# 3DChameleonMK7_2024-11-28.net
KiCad netlist of a schematic drawn in Altium Designer
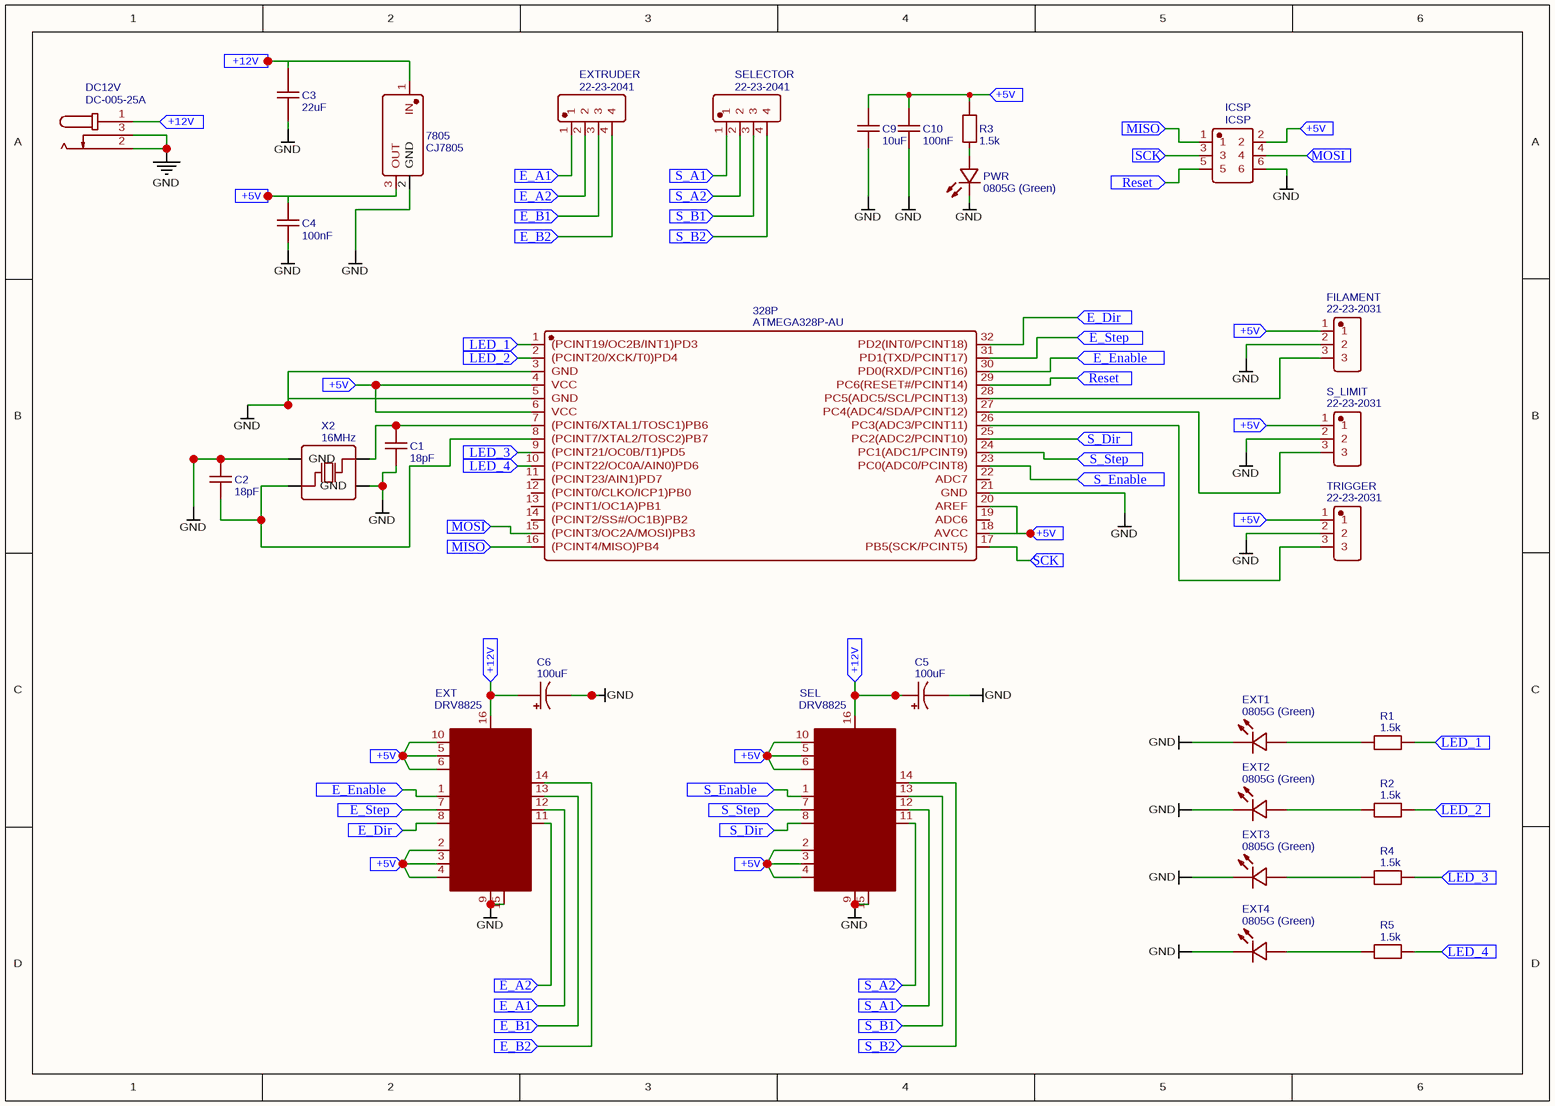
[diagram p0: 3DChameleonMK7_2024-11-28.schdoc]

(export (version "E")
  (design (tool "Eeschema 10.0.6"))
  (components
    (comp (ref "328P")
      (value "ATMEGA328P-AU")
      (fields (field (name "MANUFACTURER") "MICROCHIP"))
      (libsource (lib "altium-import") (part "root_0_ATMEGA328P-AU_"))
    )
    (comp (ref "7805")
      (value "CJ7805")
      (fields (field (name "MANUFACTURER") "CJ") (field (name "CONTRIBUTOR") "LCSC"))
      (libsource (lib "altium-import") (part "root_3_CJ7805_"))
    )
    (comp (ref "C1")
      (value "18pF")
      (fields (field (name "MANUFACTURER") "Zhejiang Abel Elec"))
      (libsource (lib "altium-import") (part "root_1_18pF_"))
    )
    (comp (ref "C2")
      (value "18pF")
      (fields (field (name "MANUFACTURER") "Zhejiang Abel Elec"))
      (libsource (lib "altium-import") (part "root_1_18pF_"))
    )
    (comp (ref "C3")
      (value "22uF")
      (fields (field (name "MANUFACTURER") "SAMSUNG") (field (name "MANUFACTURER PART") "CL21A226MAQNNNE"))
      (libsource (lib "altium-import") (part "root_1_22uF_"))
    )
    (comp (ref "C4")
      (value "100nF")
      (fields (field (name "MANUFACTURER PART") "CL21B104JBCNNNC") (field (name "MANUFACTURER") "SAMSUNG"))
      (libsource (lib "altium-import") (part "root_1_100nF_"))
    )
    (comp (ref "C5")
      (value "100uF")
      (fields
        (field (name "MANUFACTURER") "CEC")
        (field (name "MANUFACTURER PART") "CA45-B-6.3V-100uF-K")
        (field (name "CONTRIBUTOR") "LCSC")
      )
      (libsource (lib "altium-import") (part "root_1_100uF_"))
    )
    (comp (ref "C6")
      (value "100uF")
      (fields
        (field (name "MANUFACTURER") "CEC")
        (field (name "MANUFACTURER PART") "CA45-B-6.3V-100uF-K")
        (field (name "CONTRIBUTOR") "LCSC")
      )
      (libsource (lib "altium-import") (part "root_1_100uF_"))
    )
    (comp (ref "C9")
      (value "10uF")
      (fields (field (name "MANUFACTURER PART") "CL21A106KAYNNNE") (field (name "MANUFACTURER") "SAMSUNG"))
      (libsource (lib "altium-import") (part "root_1_10uF_"))
    )
    (comp (ref "C10")
      (value "100nF")
      (fields (field (name "MANUFACTURER PART") "CL21B104JBCNNNC") (field (name "MANUFACTURER") "SAMSUNG"))
      (libsource (lib "altium-import") (part "root_1_100nF_"))
    )
    (comp (ref "DC12V")
      (value "DC-005-25A")
      (fields (field (name "MANUFACTURER") "HRO") (field (name "CONTRIBUTOR") "LCSC"))
      (libsource (lib "altium-import") (part "root_0_DC-005-25A_"))
    )
    (comp (ref "EXT")
      (value "DRV8825")
      (fields (field (name "CONTRIBUTOR") "OldJeffer"))
      (libsource (lib "altium-import") (part "root_0_DRV8825_"))
    )
    (comp (ref "EXT1")
      (value "0805G (Green)")
      (fields (field (name "MANUFACTURER") "KENTO"))
      (libsource (lib "altium-import") (part "root_0_0805G (Green)_"))
    )
    (comp (ref "EXT2")
      (value "0805G (Green)")
      (fields (field (name "MANUFACTURER") "KENTO"))
      (libsource (lib "altium-import") (part "root_0_0805G (Green)_"))
    )
    (comp (ref "EXT3")
      (value "0805G (Green)")
      (fields (field (name "MANUFACTURER") "KENTO"))
      (libsource (lib "altium-import") (part "root_0_0805G (Green)_"))
    )
    (comp (ref "EXT4")
      (value "0805G (Green)")
      (fields (field (name "MANUFACTURER") "KENTO"))
      (libsource (lib "altium-import") (part "root_0_0805G (Green)_"))
    )
    (comp (ref "EXTRUDER")
      (value "22-23-2041")
      (fields (field (name "MANUFACTURER") "MOLEX") (field (name "CONTRIBUTOR") "LCSC"))
      (libsource (lib "altium-import") (part "root_1_22-23-2041_"))
    )
    (comp (ref "FILAMENT")
      (value "22-23-2031")
      (fields (field (name "MANUFACTURER") "MOLEX") (field (name "CONTRIBUTOR") "LCSC"))
      (libsource (lib "altium-import") (part "root_0_22-23-2031_"))
    )
    (comp (ref "ICSP")
      (value "ICSP")
      (fields
        (field (name "MANUFACTURER") "ReliaPro")
        (field (name "MANUFACTURER PART") "Female header/2.54mm2x3 Female header")
      )
      (libsource (lib "altium-import") (part "root_0_ICSP_"))
    )
    (comp (ref "PWR")
      (value "0805G (Green)")
      (fields (field (name "MANUFACTURER") "KENTO"))
      (libsource (lib "altium-import") (part "root_1_0805G (Green)_"))
    )
    (comp (ref "R1")
      (value "1.5k")
      (fields
        (field (name "MANUFACTURER") "RALEC")
        (field (name "MANUFACTURER PART") "RAT034700FTP")
        (field (name "CONTRIBUTOR") "LCSC")
      )
      (libsource (lib "altium-import") (part "root_2_1.5k_"))
    )
    (comp (ref "R2")
      (value "1.5k")
      (fields
        (field (name "MANUFACTURER") "RALEC")
        (field (name "MANUFACTURER PART") "RAT034700FTP")
        (field (name "CONTRIBUTOR") "LCSC")
      )
      (libsource (lib "altium-import") (part "root_2_1.5k_"))
    )
    (comp (ref "R3")
      (value "1.5k")
      (fields
        (field (name "MANUFACTURER") "RALEC")
        (field (name "MANUFACTURER PART") "RAT034700FTP")
        (field (name "CONTRIBUTOR") "LCSC")
      )
      (libsource (lib "altium-import") (part "root_1_1.5k_"))
    )
    (comp (ref "R4")
      (value "1.5k")
      (fields
        (field (name "MANUFACTURER") "RALEC")
        (field (name "MANUFACTURER PART") "RAT034700FTP")
        (field (name "CONTRIBUTOR") "LCSC")
      )
      (libsource (lib "altium-import") (part "root_2_1.5k_"))
    )
    (comp (ref "R5")
      (value "1.5k")
      (fields
        (field (name "MANUFACTURER") "RALEC")
        (field (name "MANUFACTURER PART") "RAT034700FTP")
        (field (name "CONTRIBUTOR") "LCSC")
      )
      (libsource (lib "altium-import") (part "root_2_1.5k_"))
    )
    (comp (ref "SEL")
      (value "DRV8825")
      (fields (field (name "CONTRIBUTOR") "OldJeffer"))
      (libsource (lib "altium-import") (part "root_0_DRV8825_"))
    )
    (comp (ref "SELECTOR")
      (value "22-23-2041")
      (fields (field (name "MANUFACTURER") "MOLEX") (field (name "CONTRIBUTOR") "LCSC"))
      (libsource (lib "altium-import") (part "root_1_22-23-2041_"))
    )
    (comp (ref "S_LIMIT")
      (value "22-23-2031")
      (fields (field (name "MANUFACTURER") "MOLEX") (field (name "CONTRIBUTOR") "LCSC"))
      (libsource (lib "altium-import") (part "root_0_22-23-2031_"))
    )
    (comp (ref "TRIGGER")
      (value "22-23-2031")
      (fields (field (name "MANUFACTURER") "MOLEX") (field (name "CONTRIBUTOR") "LCSC"))
      (libsource (lib "altium-import") (part "root_0_22-23-2031_"))
    )
    (comp (ref "X2")
      (value "16MHz")
      (fields
        (field (name "MANUFACTURER") "ZheJiang East Crystal Elec")
        (field (name "MANUFACTURER PART") "M16000B222")
        (field (name "CONTRIBUTOR") "LCSC")
      )
      (libsource (lib "altium-import") (part "root_0_16MHz_"))
    )
  )
  (nets
    (net (code "1") (name "/+5V") (class "Default")
      (node (ref "328P") (pin "18") (pinfunction "AVCC_18") (pintype "passive"))
      (node (ref "328P") (pin "20") (pinfunction "AREF_20") (pintype "passive"))
      (node (ref "328P") (pin "4") (pinfunction "VCC_4") (pintype "passive"))
      (node (ref "328P") (pin "6") (pinfunction "VCC_6") (pintype "passive"))
      (node (ref "7805") (pin "3") (pinfunction "OUT_3") (pintype "passive"))
      (node (ref "C10") (pin "2") (pinfunction "2_2") (pintype "passive"))
      (node (ref "C4") (pin "2") (pinfunction "2_2") (pintype "passive"))
      (node (ref "C9") (pin "2") (pinfunction "2_2") (pintype "passive"))
      (node (ref "EXT") (pin "10") (pinfunction "FLT_10") (pintype "passive"))
      (node (ref "EXT") (pin "2") (pinfunction "M0_2") (pintype "passive"))
      (node (ref "EXT") (pin "3") (pinfunction "M1_3") (pintype "passive"))
      (node (ref "EXT") (pin "4") (pinfunction "M2_4") (pintype "passive"))
      (node (ref "EXT") (pin "5") (pinfunction "RST_5") (pintype "passive"))
      (node (ref "EXT") (pin "6") (pinfunction "SLP_6") (pintype "passive"))
      (node (ref "FILAMENT") (pin "1") (pinfunction "1_1") (pintype "passive"))
      (node (ref "ICSP") (pin "2") (pinfunction "2_2") (pintype "passive"))
      (node (ref "R3") (pin "2") (pinfunction "2_2") (pintype "passive"))
      (node (ref "SEL") (pin "10") (pinfunction "FLT_10") (pintype "passive"))
      (node (ref "SEL") (pin "2") (pinfunction "M0_2") (pintype "passive"))
      (node (ref "SEL") (pin "3") (pinfunction "M1_3") (pintype "passive"))
      (node (ref "SEL") (pin "4") (pinfunction "M2_4") (pintype "passive"))
      (node (ref "SEL") (pin "5") (pinfunction "RST_5") (pintype "passive"))
      (node (ref "SEL") (pin "6") (pinfunction "SLP_6") (pintype "passive"))
      (node (ref "S_LIMIT") (pin "1") (pinfunction "1_1") (pintype "passive"))
      (node (ref "TRIGGER") (pin "1") (pinfunction "1_1") (pintype "passive"))
    )
    (net (code "2") (name "/+12V") (class "Default")
      (node (ref "7805") (pin "1") (pinfunction "IN_1") (pintype "passive"))
      (node (ref "C3") (pin "2") (pinfunction "2_2") (pintype "passive"))
      (node (ref "C5") (pin "1") (pinfunction "1_1") (pintype "passive"))
      (node (ref "C6") (pin "1") (pinfunction "1_1") (pintype "passive"))
      (node (ref "DC12V") (pin "1") (pinfunction "1_1") (pintype "passive"))
      (node (ref "EXT") (pin "16") (pinfunction "VMOT_16") (pintype "passive"))
      (node (ref "SEL") (pin "16") (pinfunction "VMOT_16") (pintype "passive"))
    )
    (net (code "3") (name "/E_A1") (class "Default")
      (node (ref "EXT") (pin "12") (pinfunction "A1_12") (pintype "passive"))
      (node (ref "EXTRUDER") (pin "1") (pinfunction "1_1") (pintype "passive"))
    )
    (net (code "4") (name "/E_A2") (class "Default")
      (node (ref "EXT") (pin "11") (pinfunction "A2_11") (pintype "passive"))
      (node (ref "EXTRUDER") (pin "2") (pinfunction "2_2") (pintype "passive"))
    )
    (net (code "5") (name "/E_B1") (class "Default")
      (node (ref "EXT") (pin "13") (pinfunction "B1_13") (pintype "passive"))
      (node (ref "EXTRUDER") (pin "3") (pinfunction "3_3") (pintype "passive"))
    )
    (net (code "6") (name "/E_B2") (class "Default")
      (node (ref "EXT") (pin "14") (pinfunction "B2_14") (pintype "passive"))
      (node (ref "EXTRUDER") (pin "4") (pinfunction "4_4") (pintype "passive"))
    )
    (net (code "7") (name "/E_Dir") (class "Default")
      (node (ref "328P") (pin "32") (pinfunction "PD2(INT0/PCINT18)_32") (pintype "passive"))
      (node (ref "EXT") (pin "8") (pinfunction "DIR_8") (pintype "passive"))
    )
    (net (code "8") (name "/E_Enable") (class "Default")
      (node (ref "328P") (pin "30") (pinfunction "PD0(RXD/PCINT16)_30") (pintype "passive"))
      (node (ref "EXT") (pin "1") (pinfunction "EN_1") (pintype "passive"))
    )
    (net (code "9") (name "/E_Step") (class "Default")
      (node (ref "328P") (pin "31") (pinfunction "PD1(TXD/PCINT17)_31") (pintype "passive"))
      (node (ref "EXT") (pin "7") (pinfunction "STEP_7") (pintype "passive"))
    )
    (net (code "10") (name "/LED_1") (class "Default")
      (node (ref "328P") (pin "1") (pinfunction "(PCINT19/OC2B/INT1)PD3_1") (pintype "passive"))
      (node (ref "R1") (pin "1") (pinfunction "1_1") (pintype "passive"))
    )
    (net (code "11") (name "/LED_2") (class "Default")
      (node (ref "328P") (pin "2") (pinfunction "(PCINT20/XCK/T0)PD4_2") (pintype "passive"))
      (node (ref "R2") (pin "1") (pinfunction "1_1") (pintype "passive"))
    )
    (net (code "12") (name "/LED_3") (class "Default")
      (node (ref "328P") (pin "9") (pinfunction "(PCINT21/OC0B/T1)PD5_9") (pintype "passive"))
      (node (ref "R4") (pin "1") (pinfunction "1_1") (pintype "passive"))
    )
    (net (code "13") (name "/LED_4") (class "Default")
      (node (ref "328P") (pin "10") (pinfunction "(PCINT22/OC0A/AIN0)PD6_10") (pintype "passive"))
      (node (ref "R5") (pin "1") (pinfunction "1_1") (pintype "passive"))
    )
    (net (code "14") (name "/MISO") (class "Default")
      (node (ref "328P") (pin "16") (pinfunction "(PCINT4/MISO)PB4_16") (pintype "passive"))
      (node (ref "ICSP") (pin "1") (pinfunction "1_1") (pintype "passive"))
    )
    (net (code "15") (name "/MOSI") (class "Default")
      (node (ref "328P") (pin "15") (pinfunction "(PCINT3/OC2A/MOSI)PB3_15") (pintype "passive"))
      (node (ref "ICSP") (pin "4") (pinfunction "4_4") (pintype "passive"))
    )
    (net (code "16") (name "/Reset") (class "Default")
      (node (ref "328P") (pin "29") (pinfunction "PC6(RESET#/PCINT14)_29") (pintype "passive"))
      (node (ref "ICSP") (pin "5") (pinfunction "5_5") (pintype "passive"))
    )
    (net (code "17") (name "/SCK") (class "Default")
      (node (ref "328P") (pin "17") (pinfunction "PB5(SCK/PCINT5)_17") (pintype "passive"))
      (node (ref "ICSP") (pin "3") (pinfunction "3_3") (pintype "passive"))
    )
    (net (code "18") (name "/S_A1") (class "Default")
      (node (ref "SEL") (pin "12") (pinfunction "A1_12") (pintype "passive"))
      (node (ref "SELECTOR") (pin "1") (pinfunction "1_1") (pintype "passive"))
    )
    (net (code "19") (name "/S_A2") (class "Default")
      (node (ref "SEL") (pin "11") (pinfunction "A2_11") (pintype "passive"))
      (node (ref "SELECTOR") (pin "2") (pinfunction "2_2") (pintype "passive"))
    )
    (net (code "20") (name "/S_B1") (class "Default")
      (node (ref "SEL") (pin "13") (pinfunction "B1_13") (pintype "passive"))
      (node (ref "SELECTOR") (pin "3") (pinfunction "3_3") (pintype "passive"))
    )
    (net (code "21") (name "/S_B2") (class "Default")
      (node (ref "SEL") (pin "14") (pinfunction "B2_14") (pintype "passive"))
      (node (ref "SELECTOR") (pin "4") (pinfunction "4_4") (pintype "passive"))
    )
    (net (code "22") (name "/S_Dir") (class "Default")
      (node (ref "328P") (pin "25") (pinfunction "PC2(ADC2/PCINT10)_25") (pintype "passive"))
      (node (ref "SEL") (pin "8") (pinfunction "DIR_8") (pintype "passive"))
    )
    (net (code "23") (name "/S_Enable") (class "Default")
      (node (ref "328P") (pin "23") (pinfunction "PC0(ADC0/PCINT8)_23") (pintype "passive"))
      (node (ref "SEL") (pin "1") (pinfunction "EN_1") (pintype "passive"))
    )
    (net (code "24") (name "/S_Step") (class "Default")
      (node (ref "328P") (pin "24") (pinfunction "PC1(ADC1/PCINT9)_24") (pintype "passive"))
      (node (ref "SEL") (pin "7") (pinfunction "STEP_7") (pintype "passive"))
    )
    (net (code "25") (name "GND") (class "Default")
      (node (ref "328P") (pin "21") (pinfunction "GND_21") (pintype "passive"))
      (node (ref "328P") (pin "3") (pinfunction "GND_3") (pintype "passive"))
      (node (ref "328P") (pin "5") (pinfunction "GND_5") (pintype "passive"))
      (node (ref "7805") (pin "2") (pinfunction "GND_2") (pintype "passive"))
      (node (ref "C1") (pin "1") (pinfunction "1_1") (pintype "passive"))
      (node (ref "C10") (pin "1") (pinfunction "1_1") (pintype "passive"))
      (node (ref "C2") (pin "2") (pinfunction "2_2") (pintype "passive"))
      (node (ref "C3") (pin "1") (pinfunction "1_1") (pintype "passive"))
      (node (ref "C4") (pin "1") (pinfunction "1_1") (pintype "passive"))
      (node (ref "C5") (pin "2") (pinfunction "2_2") (pintype "passive"))
      (node (ref "C6") (pin "2") (pinfunction "2_2") (pintype "passive"))
      (node (ref "C9") (pin "1") (pinfunction "1_1") (pintype "passive"))
      (node (ref "DC12V") (pin "2") (pinfunction "2_2") (pintype "passive"))
      (node (ref "DC12V") (pin "3") (pinfunction "3_3") (pintype "passive"))
      (node (ref "EXT") (pin "15") (pinfunction "GND_15") (pintype "passive"))
      (node (ref "EXT") (pin "9") (pinfunction "GND_9") (pintype "passive"))
      (node (ref "EXT1") (pin "1") (pinfunction "K_1") (pintype "passive"))
      (node (ref "EXT2") (pin "1") (pinfunction "K_1") (pintype "passive"))
      (node (ref "EXT3") (pin "1") (pinfunction "K_1") (pintype "passive"))
      (node (ref "EXT4") (pin "1") (pinfunction "K_1") (pintype "passive"))
      (node (ref "FILAMENT") (pin "2") (pinfunction "2_2") (pintype "passive"))
      (node (ref "ICSP") (pin "6") (pinfunction "6_6") (pintype "passive"))
      (node (ref "PWR") (pin "1") (pinfunction "K_1") (pintype "passive"))
      (node (ref "SEL") (pin "15") (pinfunction "GND_15") (pintype "passive"))
      (node (ref "SEL") (pin "9") (pinfunction "GND_9") (pintype "passive"))
      (node (ref "S_LIMIT") (pin "2") (pinfunction "2_2") (pintype "passive"))
      (node (ref "TRIGGER") (pin "2") (pinfunction "2_2") (pintype "passive"))
      (node (ref "X2") (pin "2") (pinfunction "GND_2") (pintype "passive"))
      (node (ref "X2") (pin "4") (pinfunction "GND_4") (pintype "passive"))
    )
    (net (code "26") (name "Net-(328P-(PCINT6{slash}XTAL1{slash}TOSC1)PB6)") (class "Default")
      (node (ref "328P") (pin "7") (pinfunction "(PCINT6/XTAL1/TOSC1)PB6_7") (pintype "passive"))
      (node (ref "C1") (pin "2") (pinfunction "2_2") (pintype "passive"))
      (node (ref "X2") (pin "3") (pinfunction "OSC2_3") (pintype "passive"))
    )
    (net (code "27") (name "Net-(328P-(PCINT7{slash}XTAL2{slash}TOSC2)PB7)") (class "Default")
      (node (ref "328P") (pin "8") (pinfunction "(PCINT7/XTAL2/TOSC2)PB7_8") (pintype "passive"))
      (node (ref "C2") (pin "1") (pinfunction "1_1") (pintype "passive"))
      (node (ref "X2") (pin "1") (pinfunction "OSC1_1") (pintype "passive"))
    )
    (net (code "28") (name "Net-(328P-PC3(ADC3{slash}PCINT11))") (class "Default")
      (node (ref "328P") (pin "26") (pinfunction "PC3(ADC3/PCINT11)_26") (pintype "passive"))
      (node (ref "TRIGGER") (pin "3") (pinfunction "3_3") (pintype "passive"))
    )
    (net (code "29") (name "Net-(328P-PC4(ADC4{slash}SDA{slash}PCINT12))") (class "Default")
      (node (ref "328P") (pin "27") (pinfunction "PC4(ADC4/SDA/PCINT12)_27") (pintype "passive"))
      (node (ref "S_LIMIT") (pin "3") (pinfunction "3_3") (pintype "passive"))
    )
    (net (code "30") (name "Net-(328P-PC5(ADC5{slash}SCL{slash}PCINT13))") (class "Default")
      (node (ref "328P") (pin "28") (pinfunction "PC5(ADC5/SCL/PCINT13)_28") (pintype "passive"))
      (node (ref "FILAMENT") (pin "3") (pinfunction "3_3") (pintype "passive"))
    )
    (net (code "31") (name "Net-(EXT1-A)") (class "Default")
      (node (ref "EXT1") (pin "2") (pinfunction "A_2") (pintype "passive"))
      (node (ref "R1") (pin "2") (pinfunction "2_2") (pintype "passive"))
    )
    (net (code "32") (name "Net-(EXT2-A)") (class "Default")
      (node (ref "EXT2") (pin "2") (pinfunction "A_2") (pintype "passive"))
      (node (ref "R2") (pin "2") (pinfunction "2_2") (pintype "passive"))
    )
    (net (code "33") (name "Net-(EXT3-A)") (class "Default")
      (node (ref "EXT3") (pin "2") (pinfunction "A_2") (pintype "passive"))
      (node (ref "R4") (pin "2") (pinfunction "2_2") (pintype "passive"))
    )
    (net (code "34") (name "Net-(EXT4-A)") (class "Default")
      (node (ref "EXT4") (pin "2") (pinfunction "A_2") (pintype "passive"))
      (node (ref "R5") (pin "2") (pinfunction "2_2") (pintype "passive"))
    )
    (net (code "35") (name "Net-(PWR-A)") (class "Default")
      (node (ref "PWR") (pin "2") (pinfunction "A_2") (pintype "passive"))
      (node (ref "R3") (pin "1") (pinfunction "1_1") (pintype "passive"))
    )
    (net (code "36") (name "unconnected-(328P-(PCINT0{slash}CLKO{slash}ICP1)PB0-Pad12)") (class "Default")
      (node (ref "328P") (pin "12") (pinfunction "(PCINT0/CLKO/ICP1)PB0_12") (pintype "passive"))
    )
    (net (code "37") (name "unconnected-(328P-(PCINT1{slash}OC1A)PB1-Pad13)") (class "Default")
      (node (ref "328P") (pin "13") (pinfunction "(PCINT1/OC1A)PB1_13") (pintype "passive"))
    )
    (net (code "38") (name "unconnected-(328P-(PCINT2{slash}SS#{slash}OC1B)PB2-Pad14)") (class "Default")
      (node (ref "328P") (pin "14") (pinfunction "(PCINT2/SS#/OC1B)PB2_14") (pintype "passive"))
    )
    (net (code "39") (name "unconnected-(328P-(PCINT23{slash}AIN1)PD7-Pad11)") (class "Default")
      (node (ref "328P") (pin "11") (pinfunction "(PCINT23/AIN1)PD7_11") (pintype "passive"))
    )
    (net (code "40") (name "unconnected-(328P-ADC6-Pad19)") (class "Default")
      (node (ref "328P") (pin "19") (pinfunction "ADC6_19") (pintype "passive"))
    )
    (net (code "41") (name "unconnected-(328P-ADC7-Pad22)") (class "Default")
      (node (ref "328P") (pin "22") (pinfunction "ADC7_22") (pintype "passive"))
    )
  )
)
